# MicroPomodoro.net
KiCad netlist of a schematic drawn in EAGLE
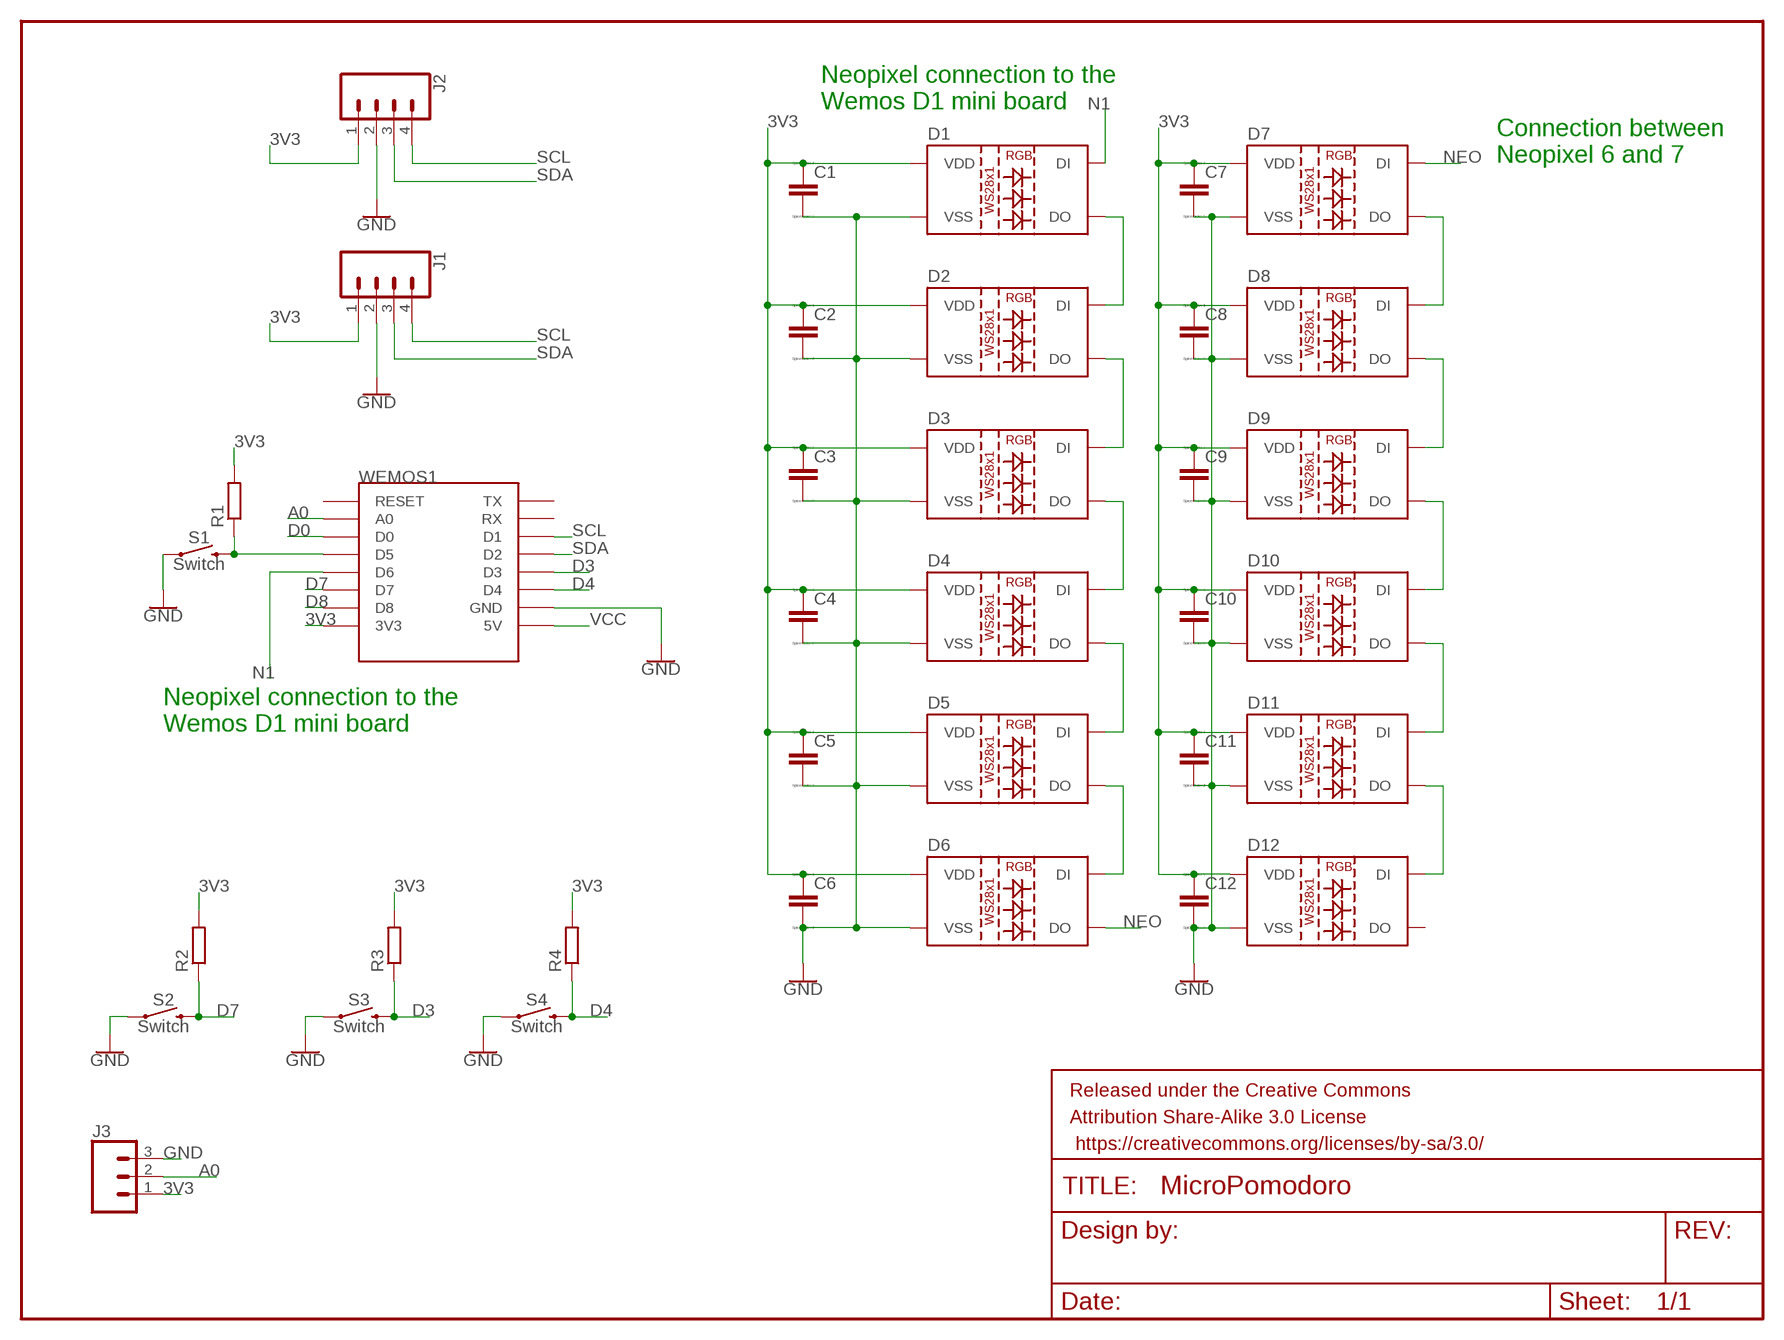
[diagram p0: schematic, sheet 1]

(export (version "E")
  (design (tool "Eeschema 10.0.6"))
  (components
    (comp (ref "C1")
      (value "CC1206")
      (footprint "eagle-import:C1206")
      (libsource (lib "eagle-import") (part "CC1206"))
    )
    (comp (ref "C2")
      (value "CC1206")
      (footprint "eagle-import:C1206")
      (libsource (lib "eagle-import") (part "CC1206"))
    )
    (comp (ref "C3")
      (value "CC1206")
      (footprint "eagle-import:C1206")
      (libsource (lib "eagle-import") (part "CC1206"))
    )
    (comp (ref "C4")
      (value "CC1206")
      (footprint "eagle-import:C1206")
      (libsource (lib "eagle-import") (part "CC1206"))
    )
    (comp (ref "C5")
      (value "CC1206")
      (footprint "eagle-import:C1206")
      (libsource (lib "eagle-import") (part "CC1206"))
    )
    (comp (ref "C6")
      (value "CC1206")
      (footprint "eagle-import:C1206")
      (libsource (lib "eagle-import") (part "CC1206"))
    )
    (comp (ref "C7")
      (value "CC1206")
      (footprint "eagle-import:C1206")
      (libsource (lib "eagle-import") (part "CC1206"))
    )
    (comp (ref "C8")
      (value "CC1206")
      (footprint "eagle-import:C1206")
      (libsource (lib "eagle-import") (part "CC1206"))
    )
    (comp (ref "C9")
      (value "CC1206")
      (footprint "eagle-import:C1206")
      (libsource (lib "eagle-import") (part "CC1206"))
    )
    (comp (ref "C10")
      (value "CC1206")
      (footprint "eagle-import:C1206")
      (libsource (lib "eagle-import") (part "CC1206"))
    )
    (comp (ref "C11")
      (value "CC1206")
      (footprint "eagle-import:C1206")
      (libsource (lib "eagle-import") (part "CC1206"))
    )
    (comp (ref "C12")
      (value "CC1206")
      (footprint "eagle-import:C1206")
      (libsource (lib "eagle-import") (part "CC1206"))
    )
    (comp (ref "D1")
      (value "WS2812B")
      (footprint "eagle-import:WS2812B")
      (libsource (lib "eagle-import") (part "WS2812B"))
    )
    (comp (ref "D2")
      (value "WS2812B")
      (footprint "eagle-import:WS2812B")
      (libsource (lib "eagle-import") (part "WS2812B"))
    )
    (comp (ref "D3")
      (value "WS2812B")
      (footprint "eagle-import:WS2812B")
      (libsource (lib "eagle-import") (part "WS2812B"))
    )
    (comp (ref "D4")
      (value "WS2812B")
      (footprint "eagle-import:WS2812B")
      (libsource (lib "eagle-import") (part "WS2812B"))
    )
    (comp (ref "D5")
      (value "WS2812B")
      (footprint "eagle-import:WS2812B")
      (libsource (lib "eagle-import") (part "WS2812B"))
    )
    (comp (ref "D6")
      (value "WS2812B")
      (footprint "eagle-import:WS2812B")
      (libsource (lib "eagle-import") (part "WS2812B"))
    )
    (comp (ref "D7")
      (value "WS2812B")
      (footprint "eagle-import:WS2812B")
      (libsource (lib "eagle-import") (part "WS2812B"))
    )
    (comp (ref "D8")
      (value "WS2812B")
      (footprint "eagle-import:WS2812B")
      (libsource (lib "eagle-import") (part "WS2812B"))
    )
    (comp (ref "D9")
      (value "WS2812B")
      (footprint "eagle-import:WS2812B")
      (libsource (lib "eagle-import") (part "WS2812B"))
    )
    (comp (ref "D10")
      (value "WS2812B")
      (footprint "eagle-import:WS2812B")
      (libsource (lib "eagle-import") (part "WS2812B"))
    )
    (comp (ref "D11")
      (value "WS2812B")
      (footprint "eagle-import:WS2812B")
      (libsource (lib "eagle-import") (part "WS2812B"))
    )
    (comp (ref "D12")
      (value "WS2812B")
      (footprint "eagle-import:WS2812B")
      (libsource (lib "eagle-import") (part "WS2812B"))
    )
    (comp (ref "FRAME1")
      (value "FRAME-LETTER")
      (footprint "eagle-import:CREATIVE_COMMONS")
      (libsource (lib "eagle-import") (part "FRAME-LETTER"))
    )
    (comp (ref "J1")
      (value "CONN_04LONGPADS")
      (footprint "eagle-import:1X04_LONGPADS")
      (libsource (lib "eagle-import") (part "CONN_04LONGPADS"))
    )
    (comp (ref "J2")
      (value "CONN_04SMD_LONG")
      (footprint "eagle-import:1X04_SMD_LONG_NO_HOLE")
      (libsource (lib "eagle-import") (part "CONN_04SMD_LONG"))
    )
    (comp (ref "J3")
      (value "CONN_03SMD_RA_MALE")
      (footprint "eagle-import:1X03_SMD_RA_MALE")
      (libsource (lib "eagle-import") (part "CONN_03SMD_RA_MALE"))
    )
    (comp (ref "R1")
      (value "R-EU_R1206")
      (footprint "eagle-import:R1206")
      (libsource (lib "eagle-import") (part "R-EU_R1206"))
    )
    (comp (ref "R2")
      (value "R-EU_R1206")
      (footprint "eagle-import:R1206")
      (libsource (lib "eagle-import") (part "R-EU_R1206"))
    )
    (comp (ref "R3")
      (value "R-EU_R1206")
      (footprint "eagle-import:R1206")
      (libsource (lib "eagle-import") (part "R-EU_R1206"))
    )
    (comp (ref "R4")
      (value "R-EU_R1206")
      (footprint "eagle-import:R1206")
      (libsource (lib "eagle-import") (part "R-EU_R1206"))
    )
    (comp (ref "S1")
      (value "Switch")
      (footprint "eagle-import:TACTILE_SWITCH_PTH_6.0MM")
      (libsource (lib "eagle-import") (part "MOMENTARY-SWITCH-SPST-PTH-6.0MM"))
    )
    (comp (ref "S2")
      (value "Switch")
      (footprint "eagle-import:TACTILE_SWITCH_PTH_6.0MM")
      (libsource (lib "eagle-import") (part "MOMENTARY-SWITCH-SPST-PTH-6.0MM"))
    )
    (comp (ref "S3")
      (value "Switch")
      (footprint "eagle-import:TACTILE_SWITCH_PTH_6.0MM")
      (libsource (lib "eagle-import") (part "MOMENTARY-SWITCH-SPST-PTH-6.0MM"))
    )
    (comp (ref "S4")
      (value "Switch")
      (footprint "eagle-import:TACTILE_SWITCH_PTH_6.0MM")
      (libsource (lib "eagle-import") (part "MOMENTARY-SWITCH-SPST-PTH-6.0MM"))
    )
    (comp (ref "WEMOS1")
      (value "WEMOS-D1-MINI")
      (footprint "eagle-import:WEMOS-D1-MINI")
      (libsource (lib "eagle-import") (part "WEMOS-D1-MINI"))
    )
  )
  (nets
    (net (code "1") (name "/3V3") (class "Default")
      (node (ref "C1") (pin "1") (pinfunction "1_1") (pintype "passive"))
      (node (ref "C10") (pin "1") (pinfunction "1_1") (pintype "passive"))
      (node (ref "C11") (pin "1") (pinfunction "1_1") (pintype "passive"))
      (node (ref "C12") (pin "1") (pinfunction "1_1") (pintype "passive"))
      (node (ref "C2") (pin "1") (pinfunction "1_1") (pintype "passive"))
      (node (ref "C3") (pin "1") (pinfunction "1_1") (pintype "passive"))
      (node (ref "C4") (pin "1") (pinfunction "1_1") (pintype "passive"))
      (node (ref "C5") (pin "1") (pinfunction "1_1") (pintype "passive"))
      (node (ref "C6") (pin "1") (pinfunction "1_1") (pintype "passive"))
      (node (ref "C7") (pin "1") (pinfunction "1_1") (pintype "passive"))
      (node (ref "C8") (pin "1") (pinfunction "1_1") (pintype "passive"))
      (node (ref "C9") (pin "1") (pinfunction "1_1") (pintype "passive"))
      (node (ref "D1") (pin "1") (pinfunction "VDD_1") (pintype "bidirectional"))
      (node (ref "D10") (pin "1") (pinfunction "VDD_1") (pintype "bidirectional"))
      (node (ref "D11") (pin "1") (pinfunction "VDD_1") (pintype "bidirectional"))
      (node (ref "D12") (pin "1") (pinfunction "VDD_1") (pintype "bidirectional"))
      (node (ref "D2") (pin "1") (pinfunction "VDD_1") (pintype "bidirectional"))
      (node (ref "D3") (pin "1") (pinfunction "VDD_1") (pintype "bidirectional"))
      (node (ref "D4") (pin "1") (pinfunction "VDD_1") (pintype "bidirectional"))
      (node (ref "D5") (pin "1") (pinfunction "VDD_1") (pintype "bidirectional"))
      (node (ref "D6") (pin "1") (pinfunction "VDD_1") (pintype "bidirectional"))
      (node (ref "D7") (pin "1") (pinfunction "VDD_1") (pintype "bidirectional"))
      (node (ref "D8") (pin "1") (pinfunction "VDD_1") (pintype "bidirectional"))
      (node (ref "D9") (pin "1") (pinfunction "VDD_1") (pintype "bidirectional"))
      (node (ref "J1") (pin "1") (pinfunction "1_1") (pintype "passive"))
      (node (ref "J2") (pin "1") (pinfunction "1_1") (pintype "passive"))
      (node (ref "J3") (pin "1") (pinfunction "1_1") (pintype "passive"))
      (node (ref "R1") (pin "2") (pinfunction "2_2") (pintype "passive"))
      (node (ref "R2") (pin "2") (pinfunction "2_2") (pintype "passive"))
      (node (ref "R3") (pin "2") (pinfunction "2_2") (pintype "passive"))
      (node (ref "R4") (pin "2") (pinfunction "2_2") (pintype "passive"))
      (node (ref "WEMOS1") (pin "3V3") (pinfunction "3V3_3V3") (pintype "bidirectional"))
    )
    (net (code "2") (name "/A0") (class "Default")
      (node (ref "J3") (pin "2") (pinfunction "2_2") (pintype "passive"))
      (node (ref "WEMOS1") (pin "A0") (pinfunction "A0_A0") (pintype "bidirectional"))
    )
    (net (code "3") (name "/D0") (class "Default")
      (node (ref "WEMOS1") (pin "D0") (pinfunction "D0_D0") (pintype "bidirectional"))
    )
    (net (code "4") (name "/D3") (class "Default")
      (node (ref "R3") (pin "1") (pinfunction "1_1") (pintype "passive"))
      (node (ref "S3") (pin "3") (pinfunction "2_3") (pintype "passive"))
      (node (ref "WEMOS1") (pin "D3") (pinfunction "D3_D3") (pintype "bidirectional"))
    )
    (net (code "5") (name "/D4") (class "Default")
      (node (ref "R4") (pin "1") (pinfunction "1_1") (pintype "passive"))
      (node (ref "S4") (pin "3") (pinfunction "2_3") (pintype "passive"))
      (node (ref "WEMOS1") (pin "D4") (pinfunction "D4_D4") (pintype "bidirectional"))
    )
    (net (code "6") (name "/D7") (class "Default")
      (node (ref "R2") (pin "1") (pinfunction "1_1") (pintype "passive"))
      (node (ref "S2") (pin "3") (pinfunction "2_3") (pintype "passive"))
      (node (ref "WEMOS1") (pin "D7") (pinfunction "D7_D7") (pintype "bidirectional"))
    )
    (net (code "7") (name "/D8") (class "Default")
      (node (ref "WEMOS1") (pin "D8") (pinfunction "D8_D8") (pintype "bidirectional"))
    )
    (net (code "8") (name "/N1") (class "Default")
      (node (ref "D1") (pin "4") (pinfunction "DI_4") (pintype "bidirectional"))
      (node (ref "WEMOS1") (pin "D6") (pinfunction "D6_D6") (pintype "bidirectional"))
    )
    (net (code "9") (name "/NEO") (class "Default")
      (node (ref "D6") (pin "2") (pinfunction "DO_2") (pintype "bidirectional"))
      (node (ref "D7") (pin "4") (pinfunction "DI_4") (pintype "bidirectional"))
    )
    (net (code "10") (name "/SCL") (class "Default")
      (node (ref "J1") (pin "4") (pinfunction "4_4") (pintype "passive"))
      (node (ref "J2") (pin "4") (pinfunction "4_4") (pintype "passive"))
      (node (ref "WEMOS1") (pin "D1") (pinfunction "D1_D1") (pintype "bidirectional"))
    )
    (net (code "11") (name "/SDA") (class "Default")
      (node (ref "J1") (pin "3") (pinfunction "3_3") (pintype "passive"))
      (node (ref "J2") (pin "3") (pinfunction "3_3") (pintype "passive"))
      (node (ref "WEMOS1") (pin "D2") (pinfunction "D2_D2") (pintype "bidirectional"))
    )
    (net (code "12") (name "/VCC") (class "Default")
      (node (ref "WEMOS1") (pin "5V") (pinfunction "5V_5V") (pintype "bidirectional"))
    )
    (net (code "13") (name "GND") (class "Default")
      (node (ref "C1") (pin "2") (pinfunction "2_2") (pintype "passive"))
      (node (ref "C10") (pin "2") (pinfunction "2_2") (pintype "passive"))
      (node (ref "C11") (pin "2") (pinfunction "2_2") (pintype "passive"))
      (node (ref "C12") (pin "2") (pinfunction "2_2") (pintype "passive"))
      (node (ref "C2") (pin "2") (pinfunction "2_2") (pintype "passive"))
      (node (ref "C3") (pin "2") (pinfunction "2_2") (pintype "passive"))
      (node (ref "C4") (pin "2") (pinfunction "2_2") (pintype "passive"))
      (node (ref "C5") (pin "2") (pinfunction "2_2") (pintype "passive"))
      (node (ref "C6") (pin "2") (pinfunction "2_2") (pintype "passive"))
      (node (ref "C7") (pin "2") (pinfunction "2_2") (pintype "passive"))
      (node (ref "C8") (pin "2") (pinfunction "2_2") (pintype "passive"))
      (node (ref "C9") (pin "2") (pinfunction "2_2") (pintype "passive"))
      (node (ref "D1") (pin "3") (pinfunction "VSS_3") (pintype "bidirectional"))
      (node (ref "D10") (pin "3") (pinfunction "VSS_3") (pintype "bidirectional"))
      (node (ref "D11") (pin "3") (pinfunction "VSS_3") (pintype "bidirectional"))
      (node (ref "D12") (pin "3") (pinfunction "VSS_3") (pintype "bidirectional"))
      (node (ref "D2") (pin "3") (pinfunction "VSS_3") (pintype "bidirectional"))
      (node (ref "D3") (pin "3") (pinfunction "VSS_3") (pintype "bidirectional"))
      (node (ref "D4") (pin "3") (pinfunction "VSS_3") (pintype "bidirectional"))
      (node (ref "D5") (pin "3") (pinfunction "VSS_3") (pintype "bidirectional"))
      (node (ref "D6") (pin "3") (pinfunction "VSS_3") (pintype "bidirectional"))
      (node (ref "D7") (pin "3") (pinfunction "VSS_3") (pintype "bidirectional"))
      (node (ref "D8") (pin "3") (pinfunction "VSS_3") (pintype "bidirectional"))
      (node (ref "D9") (pin "3") (pinfunction "VSS_3") (pintype "bidirectional"))
      (node (ref "J1") (pin "2") (pinfunction "2_2") (pintype "passive"))
      (node (ref "J2") (pin "2") (pinfunction "2_2") (pintype "passive"))
      (node (ref "J3") (pin "3") (pinfunction "3_3") (pintype "passive"))
      (node (ref "S1") (pin "1") (pinfunction "1_1") (pintype "passive"))
      (node (ref "S2") (pin "1") (pinfunction "1_1") (pintype "passive"))
      (node (ref "S3") (pin "1") (pinfunction "1_1") (pintype "passive"))
      (node (ref "S4") (pin "1") (pinfunction "1_1") (pintype "passive"))
      (node (ref "WEMOS1") (pin "GND") (pinfunction "GND_GND") (pintype "bidirectional"))
    )
    (net (code "14") (name "Net-(D1-DO)") (class "Default")
      (node (ref "D1") (pin "2") (pinfunction "DO_2") (pintype "bidirectional"))
      (node (ref "D2") (pin "4") (pinfunction "DI_4") (pintype "bidirectional"))
    )
    (net (code "15") (name "Net-(D2-DO)") (class "Default")
      (node (ref "D2") (pin "2") (pinfunction "DO_2") (pintype "bidirectional"))
      (node (ref "D3") (pin "4") (pinfunction "DI_4") (pintype "bidirectional"))
    )
    (net (code "16") (name "Net-(D3-DO)") (class "Default")
      (node (ref "D3") (pin "2") (pinfunction "DO_2") (pintype "bidirectional"))
      (node (ref "D4") (pin "4") (pinfunction "DI_4") (pintype "bidirectional"))
    )
    (net (code "17") (name "Net-(D4-DO)") (class "Default")
      (node (ref "D4") (pin "2") (pinfunction "DO_2") (pintype "bidirectional"))
      (node (ref "D5") (pin "4") (pinfunction "DI_4") (pintype "bidirectional"))
    )
    (net (code "18") (name "Net-(D5-DO)") (class "Default")
      (node (ref "D5") (pin "2") (pinfunction "DO_2") (pintype "bidirectional"))
      (node (ref "D6") (pin "4") (pinfunction "DI_4") (pintype "bidirectional"))
    )
    (net (code "19") (name "Net-(D7-DO)") (class "Default")
      (node (ref "D7") (pin "2") (pinfunction "DO_2") (pintype "bidirectional"))
      (node (ref "D8") (pin "4") (pinfunction "DI_4") (pintype "bidirectional"))
    )
    (net (code "20") (name "Net-(D8-DO)") (class "Default")
      (node (ref "D8") (pin "2") (pinfunction "DO_2") (pintype "bidirectional"))
      (node (ref "D9") (pin "4") (pinfunction "DI_4") (pintype "bidirectional"))
    )
    (net (code "21") (name "Net-(D10-DI)") (class "Default")
      (node (ref "D10") (pin "4") (pinfunction "DI_4") (pintype "bidirectional"))
      (node (ref "D9") (pin "2") (pinfunction "DO_2") (pintype "bidirectional"))
    )
    (net (code "22") (name "Net-(D10-DO)") (class "Default")
      (node (ref "D10") (pin "2") (pinfunction "DO_2") (pintype "bidirectional"))
      (node (ref "D11") (pin "4") (pinfunction "DI_4") (pintype "bidirectional"))
    )
    (net (code "23") (name "Net-(D11-DO)") (class "Default")
      (node (ref "D11") (pin "2") (pinfunction "DO_2") (pintype "bidirectional"))
      (node (ref "D12") (pin "4") (pinfunction "DI_4") (pintype "bidirectional"))
    )
    (net (code "24") (name "Net-(S1-2)") (class "Default")
      (node (ref "R1") (pin "1") (pinfunction "1_1") (pintype "passive"))
      (node (ref "S1") (pin "3") (pinfunction "2_3") (pintype "passive"))
      (node (ref "WEMOS1") (pin "D5") (pinfunction "D5_D5") (pintype "bidirectional"))
    )
    (net (code "25") (name "unconnected-(D12-DO-Pad2)") (class "Default")
      (node (ref "D12") (pin "2") (pinfunction "DO_2") (pintype "bidirectional"))
    )
    (net (code "26") (name "unconnected-(WEMOS1-PadRESET)") (class "Default")
      (node (ref "WEMOS1") (pin "RESET") (pinfunction "RESET_RESET") (pintype "bidirectional"))
    )
    (net (code "27") (name "unconnected-(WEMOS1-PadRX)") (class "Default")
      (node (ref "WEMOS1") (pin "RX") (pinfunction "RX_RX") (pintype "bidirectional"))
    )
    (net (code "28") (name "unconnected-(WEMOS1-PadTX)") (class "Default")
      (node (ref "WEMOS1") (pin "TX") (pinfunction "TX_TX") (pintype "bidirectional"))
    )
  )
)
